# nfc-epd-mcu.net
KiCad netlist of a schematic drawn in Altium Designer
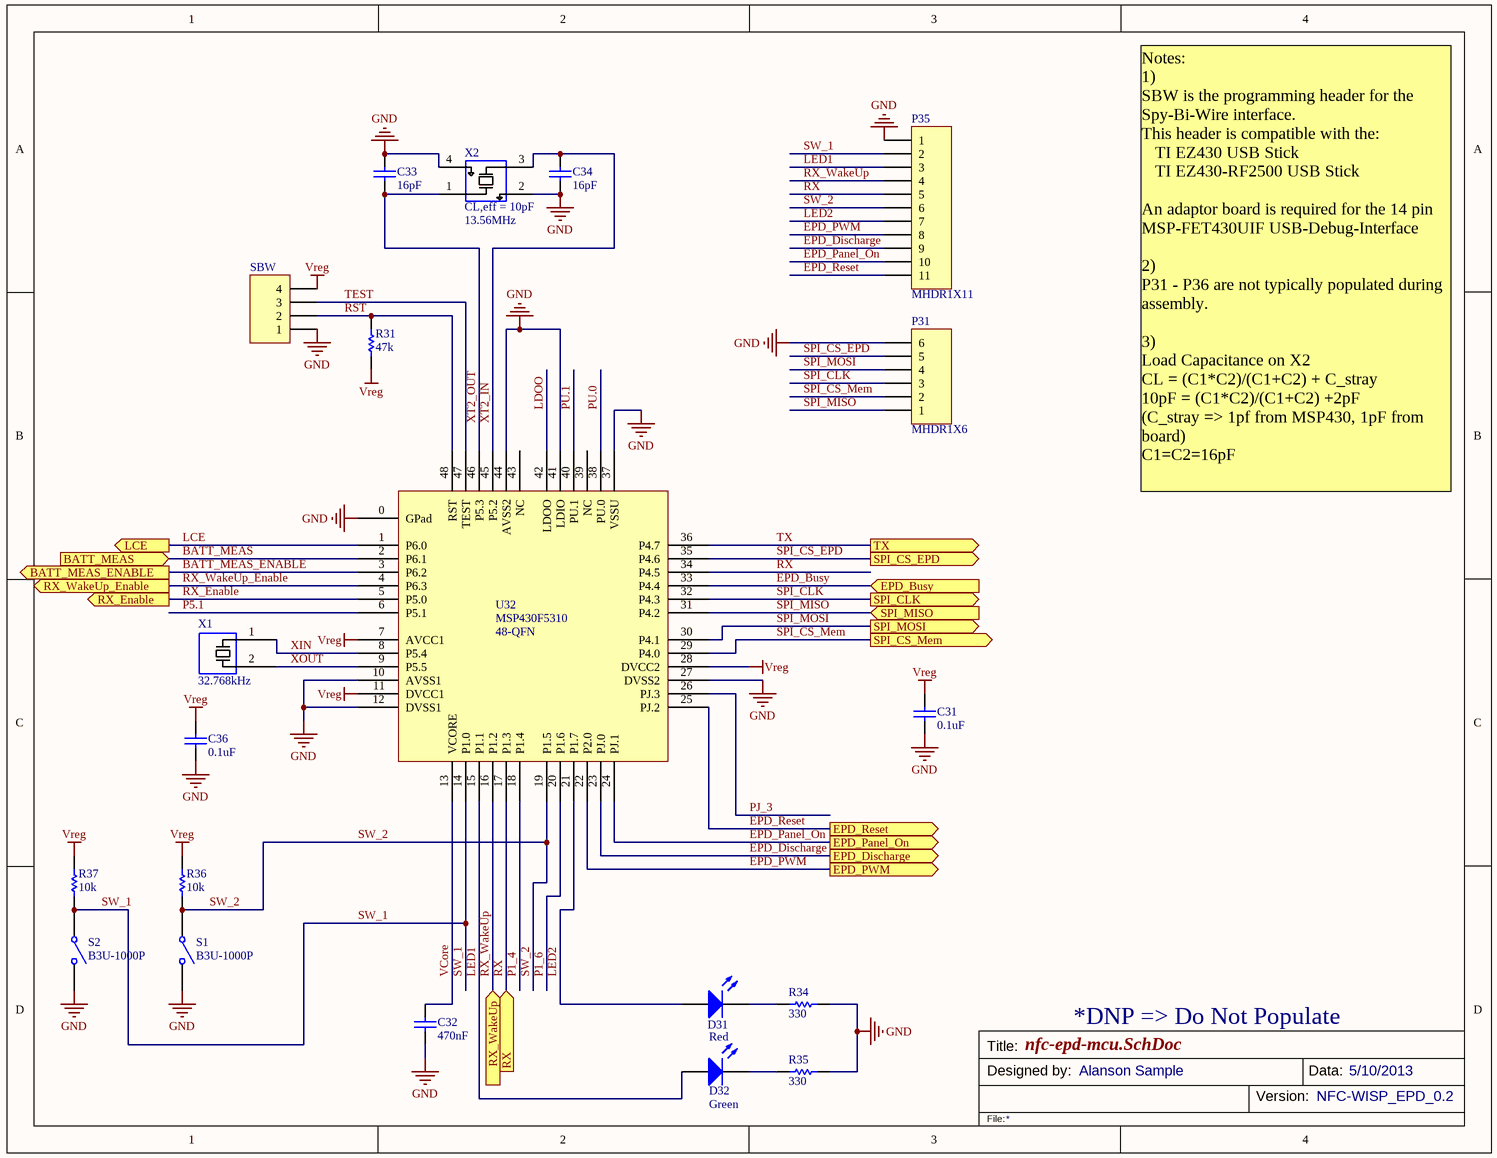
[diagram p0: nfc-epd-mcu.SchDoc]

(export (version "E")
  (design (tool "Eeschema 10.0.6"))
  (components
    (comp (ref "C31")
      (value "0.1uF")
      (footprint "0603")
      (description "Ceramic Capacitor (Surface Mount)")
      (fields (field (name "MANUFACTURER") "Generic Ceramic Chip Cap (TBD)") (field (name "Comment") "Cap"))
      (libsource (lib "WISP_AD10") (part "Cap"))
    )
    (comp (ref "C32")
      (value "470nF")
      (footprint "0603")
      (description "Ceramic Capacitor (Surface Mount)")
      (fields (field (name "MANUFACTURER") "Generic Ceramic Chip Cap (TBD)") (field (name "Comment") "Cap"))
      (libsource (lib "WISP_AD10") (part "Cap"))
    )
    (comp (ref "C33")
      (value "16pF")
      (footprint "0603")
      (description "Ceramic Capacitor (Surface Mount)")
      (fields (field (name "MANUFACTURER") "Generic Ceramic Chip Cap (TBD)") (field (name "Comment") "Cap"))
      (libsource (lib "WISP_AD10") (part "Cap"))
    )
    (comp (ref "C34")
      (value "16pF")
      (footprint "0603")
      (description "Ceramic Capacitor (Surface Mount)")
      (fields (field (name "MANUFACTURER") "Generic Ceramic Chip Cap (TBD)") (field (name "Comment") "Cap"))
      (libsource (lib "WISP_AD10") (part "Cap"))
    )
    (comp (ref "C36")
      (value "0.1uF")
      (footprint "0402")
      (description "Ceramic Capacitor (Surface Mount)")
      (fields (field (name "MANUFACTURER") "Generic Ceramic Chip Cap (TBD)") (field (name "Comment") "Cap"))
      (libsource (lib "WISP_AD10") (part "Cap"))
    )
    (comp (ref "D31")
      (value "Red")
      (footprint "Diode - 0603")
      (description "Typical RED, GREEN, YELLOW, AMBER GaAs LED")
      (fields (field (name "Comment") "LED"))
      (libsource (lib "WISP_AD10") (part "Diode - LED"))
    )
    (comp (ref "D32")
      (value "Green")
      (footprint "Diode - 0603")
      (description "Typical RED, GREEN, YELLOW, AMBER GaAs LED")
      (fields (field (name "Comment") "LED"))
      (libsource (lib "WISP_AD10") (part "Diode - LED"))
    )
    (comp (ref "P31")
      (value "MHDR1X6")
      (footprint "MHDR1X6")
      (description "Header, 6-Pin")
      (fields (field (name "PUBLISHER") "Altium Limited"))
      (libsource (lib "Miscellaneous Connectors") (part "MHDR1X6"))
    )
    (comp (ref "P35")
      (value "MHDR1X11")
      (footprint "MHDR1X11")
      (description "Header, 11-Pin")
      (fields (field (name "PUBLISHER") "Altium Limited"))
      (libsource (lib "Miscellaneous Connectors") (part "MHDR1X11"))
    )
    (comp (ref "R31")
      (value "47k")
      (footprint "0603")
      (description "Chip Resistor (Surface Mount)")
      (fields (field (name "MANUFACTURER") "Generic Chip Res (TBD)") (field (name "Comment") "Res"))
      (libsource (lib "WISP_AD10") (part "Res"))
    )
    (comp (ref "R34")
      (value "330")
      (footprint "0603")
      (description "Chip Resistor (Surface Mount)")
      (fields (field (name "MANUFACTURER") "Generic Chip Res (TBD)") (field (name "Comment") "Res"))
      (libsource (lib "WISP_AD10") (part "Res"))
    )
    (comp (ref "R35")
      (value "330")
      (footprint "0603")
      (description "Chip Resistor (Surface Mount)")
      (fields (field (name "MANUFACTURER") "Generic Chip Res (TBD)") (field (name "Comment") "Res"))
      (libsource (lib "WISP_AD10") (part "Res"))
    )
    (comp (ref "R36")
      (value "10k")
      (footprint "0603")
      (description "Chip Resistor (Surface Mount)")
      (fields (field (name "MANUFACTURER") "Generic Chip Res (TBD)") (field (name "Comment") "Res"))
      (libsource (lib "WISP_AD10") (part "Res"))
    )
    (comp (ref "R37")
      (value "10k")
      (footprint "0603")
      (description "Chip Resistor (Surface Mount)")
      (fields (field (name "MANUFACTURER") "Generic Chip Res (TBD)") (field (name "Comment") "Res"))
      (libsource (lib "WISP_AD10") (part "Res"))
    )
    (comp (ref "S1")
      (value "B3U-1000P")
      (footprint "Switch - B3U-1000P")
      (description "Generic Single-Pole, Single-Throw Switch")
      (fields
        (field (name "MANUFACTURER") "Omron Electronics Inc-EMC Div")
        (field (name "DIGI-KEY PART NUMBER") "SW1143CT-ND")
      )
      (libsource (lib "WISP_AD10") (part "Switch - Generic SPST"))
    )
    (comp (ref "S2")
      (value "B3U-1000P")
      (footprint "Switch - B3U-1000P")
      (description "Generic Single-Pole, Single-Throw Switch")
      (fields
        (field (name "MANUFACTURER") "Omron Electronics Inc-EMC Div")
        (field (name "DIGI-KEY PART NUMBER") "SW1143CT-ND")
      )
      (libsource (lib "WISP_AD10") (part "Switch - Generic SPST"))
    )
    (comp (ref "SBW")
      (value "MHDR1X4")
      (footprint "MHDR1X4")
      (description "Header, 4-Pin")
      (fields (field (name "PUBLISHER") "Altium Limited"))
      (libsource (lib "Miscellaneous Connectors") (part "MHDR1X4"))
    )
    (comp (ref "U32")
      (value "MSP430F5310")
      (footprint "48-QFN")
      (description "MSP430 - 48LQFP or 48QFN")
      (fields
        (field (name "DIGI-KEY PART NUMBER") "296-28193-2-ND or 296-28133-1-ND")
        (field (name "MANUFACTURER") "Texas Instruments")
        (field (name "NOTE") "48-QFN")
      )
      (libsource (lib "WISP_AD10") (part "MSP430F5310 - 48Pin"))
    )
    (comp (ref "X1")
      (value "32.768kHz")
      (footprint "XTAL - 2Pin [3.2mm x 1.5mm]")
      (description "Crystal Oscillator - [3.20mm x 1.50mm]")
      (fields
        (field (name "DIGI-KEY PART NUMBER") "example: SE2413CT-ND")
        (field (name "MANUFACTURER") "Epson Toyocom Corporation")
      )
      (libsource (lib "WISP_AD10") (part "XTAL 2-pins"))
    )
    (comp (ref "X2")
      (value "13.56MHz")
      (footprint "XTAL - 4Pin [3.2MM X 2.5MM]")
      (description "Crystal - 4-Pin Surface Mount")
      (fields
        (field (name "DIGI-KEY PART NUMBER") "535-10286-1-ND")
        (field (name "MANUFACTURER PART NUMBER") "ABM8G-13.560MHZ-B4Y-T")
        (field (name "RATING") "CL,eff = 10pF")
      )
      (libsource (lib "WISP_AD10") (part "XTAL 4-pins"))
    )
  )
  (nets
    (net (code "1") (name "/BATT_MEAS") (class "Default")
      (node (ref "U32") (pin "2") (pinfunction "P6.1_2") (pintype "passive"))
    )
    (net (code "2") (name "/BATT_MEAS_ENABLE") (class "Default")
      (node (ref "U32") (pin "3") (pinfunction "P6.2_3") (pintype "passive"))
    )
    (net (code "3") (name "/EPD_Busy") (class "Default")
      (node (ref "U32") (pin "33") (pinfunction "P4.4_33") (pintype "passive"))
    )
    (net (code "4") (name "/EPD_Discharge") (class "Default")
      (node (ref "P35") (pin "9") (pinfunction "9_9") (pintype "passive"))
      (node (ref "U32") (pin "23") (pinfunction "PJ.0_23") (pintype "passive"))
    )
    (net (code "5") (name "/EPD_PWM") (class "Default")
      (node (ref "P35") (pin "8") (pinfunction "8_8") (pintype "passive"))
      (node (ref "U32") (pin "22") (pinfunction "P2.0_22") (pintype "passive"))
    )
    (net (code "6") (name "/EPD_Panel_On") (class "Default")
      (node (ref "P35") (pin "10") (pinfunction "10_10") (pintype "passive"))
      (node (ref "U32") (pin "24") (pinfunction "PJ.1_24") (pintype "passive"))
    )
    (net (code "7") (name "/EPD_Reset") (class "Default")
      (node (ref "P35") (pin "11") (pinfunction "11_11") (pintype "passive"))
      (node (ref "U32") (pin "25") (pinfunction "PJ.2_25") (pintype "passive"))
    )
    (net (code "8") (name "/LCE") (class "Default")
      (node (ref "U32") (pin "1") (pinfunction "P6.0_1") (pintype "passive"))
    )
    (net (code "9") (name "/LDOO") (class "Default")
      (node (ref "U32") (pin "42") (pinfunction "LDOO_42") (pintype "passive"))
    )
    (net (code "10") (name "/LED1") (class "Default")
      (node (ref "D32") (pin "1") (pinfunction "A_1") (pintype "passive"))
      (node (ref "P35") (pin "3") (pinfunction "3_3") (pintype "passive"))
      (node (ref "U32") (pin "15") (pinfunction "P1.1_15") (pintype "passive"))
    )
    (net (code "11") (name "/LED2") (class "Default")
      (node (ref "D31") (pin "1") (pinfunction "A_1") (pintype "passive"))
      (node (ref "P35") (pin "7") (pinfunction "7_7") (pintype "passive"))
      (node (ref "U32") (pin "21") (pinfunction "P1.7_21") (pintype "passive"))
    )
    (net (code "12") (name "/P1_4") (class "Default")
      (node (ref "U32") (pin "18") (pinfunction "P1.4_18") (pintype "passive"))
    )
    (net (code "13") (name "/P1_6") (class "Default")
      (node (ref "U32") (pin "20") (pinfunction "P1.6_20") (pintype "passive"))
    )
    (net (code "14") (name "/P5.1") (class "Default")
      (node (ref "U32") (pin "6") (pinfunction "P5.1_6") (pintype "passive"))
    )
    (net (code "15") (name "/PJ_3") (class "Default")
      (node (ref "U32") (pin "26") (pinfunction "PJ.3_26") (pintype "passive"))
    )
    (net (code "16") (name "/PU.0") (class "Default")
      (node (ref "U32") (pin "38") (pinfunction "PU.0_38") (pintype "passive"))
    )
    (net (code "17") (name "/PU.1") (class "Default")
      (node (ref "U32") (pin "40") (pinfunction "PU.1_40") (pintype "passive"))
    )
    (net (code "18") (name "/RST") (class "Default")
      (node (ref "R31") (pin "1") (pinfunction "1_1") (pintype "passive"))
      (node (ref "SBW") (pin "2") (pinfunction "2_2") (pintype "passive"))
      (node (ref "U32") (pin "48") (pinfunction "RST_48") (pintype "passive"))
    )
    (net (code "19") (name "/RX") (class "Default")
      (node (ref "P35") (pin "5") (pinfunction "5_5") (pintype "passive"))
      (node (ref "U32") (pin "17") (pinfunction "P1.3_17") (pintype "passive"))
      (node (ref "U32") (pin "34") (pinfunction "P4.5_34") (pintype "passive"))
    )
    (net (code "20") (name "/RX_Enable") (class "Default")
      (node (ref "U32") (pin "5") (pinfunction "P5.0_5") (pintype "passive"))
    )
    (net (code "21") (name "/RX_WakeUp") (class "Default")
      (node (ref "P35") (pin "4") (pinfunction "4_4") (pintype "passive"))
      (node (ref "U32") (pin "16") (pinfunction "P1.2_16") (pintype "passive"))
    )
    (net (code "22") (name "/RX_WakeUp_Enable") (class "Default")
      (node (ref "U32") (pin "4") (pinfunction "P6.3_4") (pintype "passive"))
    )
    (net (code "23") (name "/SPI_CLK") (class "Default")
      (node (ref "P31") (pin "3") (pinfunction "3_3") (pintype "passive"))
      (node (ref "U32") (pin "32") (pinfunction "P4.3_32") (pintype "passive"))
    )
    (net (code "24") (name "/SPI_CS_EPD") (class "Default")
      (node (ref "P31") (pin "5") (pinfunction "5_5") (pintype "passive"))
      (node (ref "U32") (pin "35") (pinfunction "P4.6_35") (pintype "passive"))
    )
    (net (code "25") (name "/SPI_CS_Mem") (class "Default")
      (node (ref "P31") (pin "2") (pinfunction "2_2") (pintype "passive"))
      (node (ref "U32") (pin "29") (pinfunction "P4.0_29") (pintype "passive"))
    )
    (net (code "26") (name "/SPI_MISO") (class "Default")
      (node (ref "P31") (pin "1") (pinfunction "1_1") (pintype "passive"))
      (node (ref "U32") (pin "31") (pinfunction "P4.2_31") (pintype "passive"))
    )
    (net (code "27") (name "/SPI_MOSI") (class "Default")
      (node (ref "P31") (pin "4") (pinfunction "4_4") (pintype "passive"))
      (node (ref "U32") (pin "30") (pinfunction "P4.1_30") (pintype "passive"))
    )
    (net (code "28") (name "/SW_1") (class "Default")
      (node (ref "P35") (pin "2") (pinfunction "2_2") (pintype "passive"))
      (node (ref "R37") (pin "1") (pinfunction "1_1") (pintype "passive"))
      (node (ref "S2") (pin "1") (pinfunction "COMMON_1") (pintype "passive"))
      (node (ref "U32") (pin "14") (pinfunction "P1.0_14") (pintype "passive"))
    )
    (net (code "29") (name "/SW_2") (class "Default")
      (node (ref "P35") (pin "6") (pinfunction "6_6") (pintype "passive"))
      (node (ref "R36") (pin "1") (pinfunction "1_1") (pintype "passive"))
      (node (ref "S1") (pin "1") (pinfunction "COMMON_1") (pintype "passive"))
      (node (ref "U32") (pin "19") (pinfunction "P1.5_19") (pintype "passive"))
    )
    (net (code "30") (name "/TEST") (class "Default")
      (node (ref "SBW") (pin "3") (pinfunction "3_3") (pintype "passive"))
      (node (ref "U32") (pin "47") (pinfunction "TEST_47") (pintype "passive"))
    )
    (net (code "31") (name "/TX") (class "Default")
      (node (ref "U32") (pin "36") (pinfunction "P4.7_36") (pintype "passive"))
    )
    (net (code "32") (name "/VCore") (class "Default")
      (node (ref "C32") (pin "1") (pinfunction "1_1") (pintype "passive"))
      (node (ref "U32") (pin "13") (pinfunction "VCORE_13") (pintype "passive"))
    )
    (net (code "33") (name "/XIN") (class "Default")
      (node (ref "U32") (pin "8") (pinfunction "P5.4_8") (pintype "passive"))
      (node (ref "X1") (pin "1") (pinfunction "1_1") (pintype "power_in"))
    )
    (net (code "34") (name "/XOUT") (class "Default")
      (node (ref "U32") (pin "9") (pinfunction "P5.5_9") (pintype "passive"))
      (node (ref "X1") (pin "2") (pinfunction "2_2") (pintype "power_in"))
    )
    (net (code "35") (name "/XT2_IN") (class "Default")
      (node (ref "C34") (pin "2") (pinfunction "2_2") (pintype "passive"))
      (node (ref "U32") (pin "45") (pinfunction "P5.2_45") (pintype "passive"))
      (node (ref "X2") (pin "3") (pinfunction "XOUT_3") (pintype "passive"))
    )
    (net (code "36") (name "/XT2_OUT") (class "Default")
      (node (ref "C33") (pin "1") (pinfunction "1_1") (pintype "passive"))
      (node (ref "U32") (pin "46") (pinfunction "P5.3_46") (pintype "passive"))
      (node (ref "X2") (pin "1") (pinfunction "XIN_1") (pintype "passive"))
    )
    (net (code "37") (name "GND") (class "Default")
      (node (ref "C31") (pin "1") (pinfunction "1_1") (pintype "passive"))
      (node (ref "C32") (pin "2") (pinfunction "2_2") (pintype "passive"))
      (node (ref "C33") (pin "2") (pinfunction "2_2") (pintype "passive"))
      (node (ref "C34") (pin "1") (pinfunction "1_1") (pintype "passive"))
      (node (ref "C36") (pin "1") (pinfunction "1_1") (pintype "passive"))
      (node (ref "P31") (pin "6") (pinfunction "6_6") (pintype "passive"))
      (node (ref "P35") (pin "1") (pinfunction "1_1") (pintype "passive"))
      (node (ref "R34") (pin "1") (pinfunction "1_1") (pintype "passive"))
      (node (ref "R35") (pin "1") (pinfunction "1_1") (pintype "passive"))
      (node (ref "S1") (pin "2") (pinfunction "NO_2") (pintype "passive"))
      (node (ref "S2") (pin "2") (pinfunction "NO_2") (pintype "passive"))
      (node (ref "SBW") (pin "1") (pinfunction "1_1") (pintype "passive"))
      (node (ref "U32") (pin "0") (pinfunction "GPad_0") (pintype "passive"))
      (node (ref "U32") (pin "10") (pinfunction "AVSS1_10") (pintype "passive"))
      (node (ref "U32") (pin "12") (pinfunction "DVSS1_12") (pintype "passive"))
      (node (ref "U32") (pin "27") (pinfunction "DVSS2_27") (pintype "passive"))
      (node (ref "U32") (pin "37") (pinfunction "VSSU_37") (pintype "passive"))
      (node (ref "U32") (pin "41") (pinfunction "LDIO_41") (pintype "passive"))
      (node (ref "U32") (pin "44") (pinfunction "AVSS2_44") (pintype "passive"))
      (node (ref "X2") (pin "2") (pinfunction "Gnd_2") (pintype "passive"))
      (node (ref "X2") (pin "4") (pinfunction "Gnd_4") (pintype "passive"))
    )
    (net (code "38") (name "Net-(D31-K)") (class "Default")
      (node (ref "D31") (pin "2") (pinfunction "K_2") (pintype "passive"))
      (node (ref "R34") (pin "2") (pinfunction "2_2") (pintype "passive"))
    )
    (net (code "39") (name "Net-(D32-K)") (class "Default")
      (node (ref "D32") (pin "2") (pinfunction "K_2") (pintype "passive"))
      (node (ref "R35") (pin "2") (pinfunction "2_2") (pintype "passive"))
    )
    (net (code "40") (name "Vreg") (class "Default")
      (node (ref "C31") (pin "2") (pinfunction "2_2") (pintype "passive"))
      (node (ref "C36") (pin "2") (pinfunction "2_2") (pintype "passive"))
      (node (ref "R31") (pin "2") (pinfunction "2_2") (pintype "passive"))
      (node (ref "R36") (pin "2") (pinfunction "2_2") (pintype "passive"))
      (node (ref "R37") (pin "2") (pinfunction "2_2") (pintype "passive"))
      (node (ref "SBW") (pin "4") (pinfunction "4_4") (pintype "passive"))
      (node (ref "U32") (pin "11") (pinfunction "DVCC1_11") (pintype "passive"))
      (node (ref "U32") (pin "28") (pinfunction "DVCC2_28") (pintype "passive"))
      (node (ref "U32") (pin "7") (pinfunction "AVCC1_7") (pintype "passive"))
    )
    (net (code "41") (name "unconnected-(U32-NC-Pad39)") (class "Default")
      (node (ref "U32") (pin "39") (pinfunction "NC_39") (pintype "passive"))
    )
    (net (code "42") (name "unconnected-(U32-NC-Pad43)") (class "Default")
      (node (ref "U32") (pin "43") (pinfunction "NC_43") (pintype "passive"))
    )
  )
)
